# a-star_dual_drv8801_fab.net
KiCad netlist of a schematic drawn in EAGLE
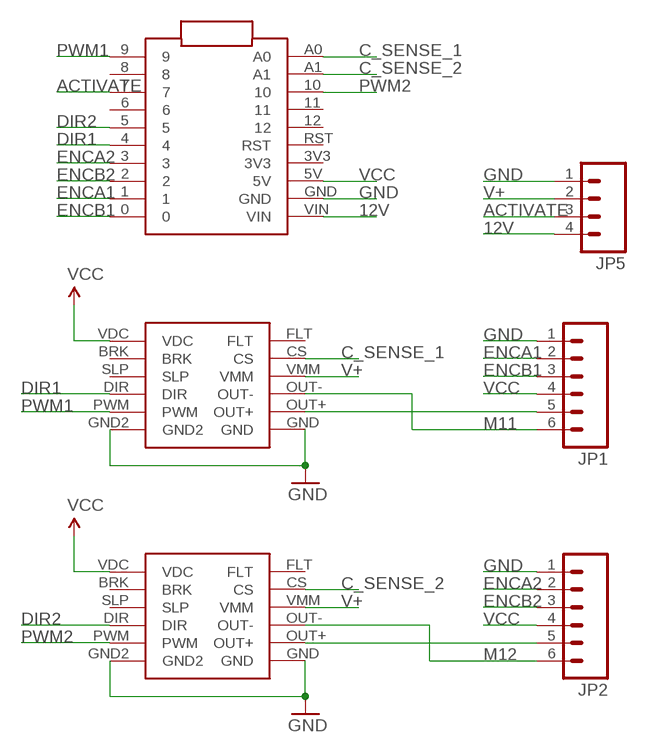
[diagram p0: schematic, sheet 1]

(export (version "E")
  (design (tool "Eeschema 10.0.6"))
  (components
    (comp (ref "JP1")
      (value "M06POLAR")
      (footprint "eagle-import:MOLEX-1X6")
      (libsource (lib "eagle-import") (part "M06POLAR"))
    )
    (comp (ref "JP2")
      (value "M06POLAR")
      (footprint "eagle-import:MOLEX-1X6")
      (libsource (lib "eagle-import") (part "M06POLAR"))
    )
    (comp (ref "JP5")
      (value "M04POLAR")
      (footprint "eagle-import:MOLEX-1X4")
      (libsource (lib "eagle-import") (part "M04POLAR"))
    )
    (comp (ref "U$1")
      (value "POLOLU_DRV8801_CARRIER")
      (footprint "eagle-import:POLOLU_DRV8801_CARRIER")
      (libsource (lib "eagle-import") (part "POLOLU_DRV8801_CARRIER"))
    )
    (comp (ref "U$2")
      (value "POLOLU_A-STAR-MICRO")
      (footprint "eagle-import:POLOLU_A-STAR-MICRO")
      (libsource (lib "eagle-import") (part "POLOLU_A-STAR-MICRO"))
    )
    (comp (ref "U$3")
      (value "POLOLU_DRV8801_CARRIER")
      (footprint "eagle-import:POLOLU_DRV8801_CARRIER")
      (libsource (lib "eagle-import") (part "POLOLU_DRV8801_CARRIER"))
    )
  )
  (nets
    (net (code "1") (name "/12V") (class "Default")
      (node (ref "JP5") (pin "4") (pinfunction "4_4") (pintype "passive"))
      (node (ref "U$2") (pin "VIN") (pinfunction "VIN_VIN") (pintype "bidirectional"))
    )
    (net (code "2") (name "/ACTIVATE") (class "Default")
      (node (ref "JP5") (pin "3") (pinfunction "3_3") (pintype "passive"))
      (node (ref "U$2") (pin "7") (pinfunction "7_7") (pintype "bidirectional"))
    )
    (net (code "3") (name "/C_SENSE_1") (class "Default")
      (node (ref "U$1") (pin "CS") (pinfunction "CS_CS") (pintype "bidirectional"))
      (node (ref "U$2") (pin "A0") (pinfunction "A0_A0") (pintype "bidirectional"))
    )
    (net (code "4") (name "/C_SENSE_2") (class "Default")
      (node (ref "U$2") (pin "A1") (pinfunction "A1_A1") (pintype "bidirectional"))
      (node (ref "U$3") (pin "CS") (pinfunction "CS_CS") (pintype "bidirectional"))
    )
    (net (code "5") (name "/DIR1") (class "Default")
      (node (ref "U$1") (pin "DIR") (pinfunction "DIR_DIR") (pintype "bidirectional"))
      (node (ref "U$2") (pin "4") (pinfunction "4_4") (pintype "bidirectional"))
    )
    (net (code "6") (name "/DIR2") (class "Default")
      (node (ref "U$2") (pin "5") (pinfunction "5_5") (pintype "bidirectional"))
      (node (ref "U$3") (pin "DIR") (pinfunction "DIR_DIR") (pintype "bidirectional"))
    )
    (net (code "7") (name "/ENCA1") (class "Default")
      (node (ref "JP1") (pin "2") (pinfunction "2_2") (pintype "passive"))
      (node (ref "U$2") (pin "1") (pinfunction "1_1") (pintype "bidirectional"))
    )
    (net (code "8") (name "/ENCA2") (class "Default")
      (node (ref "JP2") (pin "2") (pinfunction "2_2") (pintype "passive"))
      (node (ref "U$2") (pin "3") (pinfunction "3_3") (pintype "bidirectional"))
    )
    (net (code "9") (name "/ENCB1") (class "Default")
      (node (ref "JP1") (pin "3") (pinfunction "3_3") (pintype "passive"))
      (node (ref "U$2") (pin "0") (pinfunction "0_0") (pintype "bidirectional"))
    )
    (net (code "10") (name "/ENCB2") (class "Default")
      (node (ref "JP2") (pin "3") (pinfunction "3_3") (pintype "passive"))
      (node (ref "U$2") (pin "2") (pinfunction "2_2") (pintype "bidirectional"))
    )
    (net (code "11") (name "/M11") (class "Default")
      (node (ref "JP1") (pin "6") (pinfunction "6_6") (pintype "passive"))
      (node (ref "U$1") (pin "OUT-") (pinfunction "OUT-_OUT-") (pintype "bidirectional"))
    )
    (net (code "12") (name "/M12") (class "Default")
      (node (ref "JP2") (pin "6") (pinfunction "6_6") (pintype "passive"))
      (node (ref "U$3") (pin "OUT-") (pinfunction "OUT-_OUT-") (pintype "bidirectional"))
    )
    (net (code "13") (name "/PWM1") (class "Default")
      (node (ref "U$1") (pin "PWM") (pinfunction "PWM_PWM") (pintype "bidirectional"))
      (node (ref "U$2") (pin "9") (pinfunction "9_9") (pintype "bidirectional"))
    )
    (net (code "14") (name "/PWM2") (class "Default")
      (node (ref "U$2") (pin "10") (pinfunction "10_10") (pintype "bidirectional"))
      (node (ref "U$3") (pin "PWM") (pinfunction "PWM_PWM") (pintype "bidirectional"))
    )
    (net (code "15") (name "/V+") (class "Default")
      (node (ref "JP5") (pin "2") (pinfunction "2_2") (pintype "passive"))
      (node (ref "U$1") (pin "VMM") (pinfunction "VMM_VMM") (pintype "bidirectional"))
      (node (ref "U$3") (pin "VMM") (pinfunction "VMM_VMM") (pintype "bidirectional"))
    )
    (net (code "16") (name "GND") (class "Default")
      (node (ref "JP1") (pin "1") (pinfunction "1_1") (pintype "passive"))
      (node (ref "JP2") (pin "1") (pinfunction "1_1") (pintype "passive"))
      (node (ref "JP5") (pin "1") (pinfunction "1_1") (pintype "passive"))
      (node (ref "U$1") (pin "GND") (pinfunction "GND_GND") (pintype "bidirectional"))
      (node (ref "U$1") (pin "GND2") (pinfunction "GND2_GND2") (pintype "bidirectional"))
      (node (ref "U$2") (pin "GND") (pinfunction "GND_GND") (pintype "bidirectional"))
      (node (ref "U$3") (pin "GND") (pinfunction "GND_GND") (pintype "bidirectional"))
      (node (ref "U$3") (pin "GND2") (pinfunction "GND2_GND2") (pintype "bidirectional"))
    )
    (net (code "17") (name "Net-(JP1-Pad5)") (class "Default")
      (node (ref "JP1") (pin "5") (pinfunction "5_5") (pintype "passive"))
      (node (ref "U$1") (pin "OUT+") (pinfunction "OUT+_OUT+") (pintype "bidirectional"))
    )
    (net (code "18") (name "Net-(JP2-Pad5)") (class "Default")
      (node (ref "JP2") (pin "5") (pinfunction "5_5") (pintype "passive"))
      (node (ref "U$3") (pin "OUT+") (pinfunction "OUT+_OUT+") (pintype "bidirectional"))
    )
    (net (code "19") (name "VCC") (class "Default")
      (node (ref "JP1") (pin "4") (pinfunction "4_4") (pintype "passive"))
      (node (ref "JP2") (pin "4") (pinfunction "4_4") (pintype "passive"))
      (node (ref "U$1") (pin "VDC") (pinfunction "VDC_VDC") (pintype "bidirectional"))
      (node (ref "U$2") (pin "5V") (pinfunction "5V_5V") (pintype "bidirectional"))
      (node (ref "U$3") (pin "VDC") (pinfunction "VDC_VDC") (pintype "bidirectional"))
    )
    (net (code "20") (name "unconnected-(U$1-PadBRK)") (class "Default")
      (node (ref "U$1") (pin "BRK") (pinfunction "BRK_BRK") (pintype "bidirectional"))
    )
    (net (code "21") (name "unconnected-(U$1-PadFLT)") (class "Default")
      (node (ref "U$1") (pin "FLT") (pinfunction "FLT_FLT") (pintype "bidirectional"))
    )
    (net (code "22") (name "unconnected-(U$1-PadSLP)") (class "Default")
      (node (ref "U$1") (pin "SLP") (pinfunction "SLP_SLP") (pintype "bidirectional"))
    )
    (net (code "23") (name "unconnected-(U$2-Pad3V3)") (class "Default")
      (node (ref "U$2") (pin "3V3") (pinfunction "3V3_3V3") (pintype "bidirectional"))
    )
    (net (code "24") (name "unconnected-(U$2-Pad6)") (class "Default")
      (node (ref "U$2") (pin "6") (pinfunction "6_6") (pintype "bidirectional"))
    )
    (net (code "25") (name "unconnected-(U$2-Pad8)") (class "Default")
      (node (ref "U$2") (pin "8") (pinfunction "8_8") (pintype "bidirectional"))
    )
    (net (code "26") (name "unconnected-(U$2-Pad11)") (class "Default")
      (node (ref "U$2") (pin "11") (pinfunction "11_11") (pintype "bidirectional"))
    )
    (net (code "27") (name "unconnected-(U$2-Pad12)") (class "Default")
      (node (ref "U$2") (pin "12") (pinfunction "12_12") (pintype "bidirectional"))
    )
    (net (code "28") (name "unconnected-(U$2-PadRST)") (class "Default")
      (node (ref "U$2") (pin "RST") (pinfunction "RST_RST") (pintype "bidirectional"))
    )
    (net (code "29") (name "unconnected-(U$3-PadBRK)") (class "Default")
      (node (ref "U$3") (pin "BRK") (pinfunction "BRK_BRK") (pintype "bidirectional"))
    )
    (net (code "30") (name "unconnected-(U$3-PadFLT)") (class "Default")
      (node (ref "U$3") (pin "FLT") (pinfunction "FLT_FLT") (pintype "bidirectional"))
    )
    (net (code "31") (name "unconnected-(U$3-PadSLP)") (class "Default")
      (node (ref "U$3") (pin "SLP") (pinfunction "SLP_SLP") (pintype "bidirectional"))
    )
  )
)
